# V1_USB_sch.net
KiCad netlist of a schematic drawn in Altium Designer
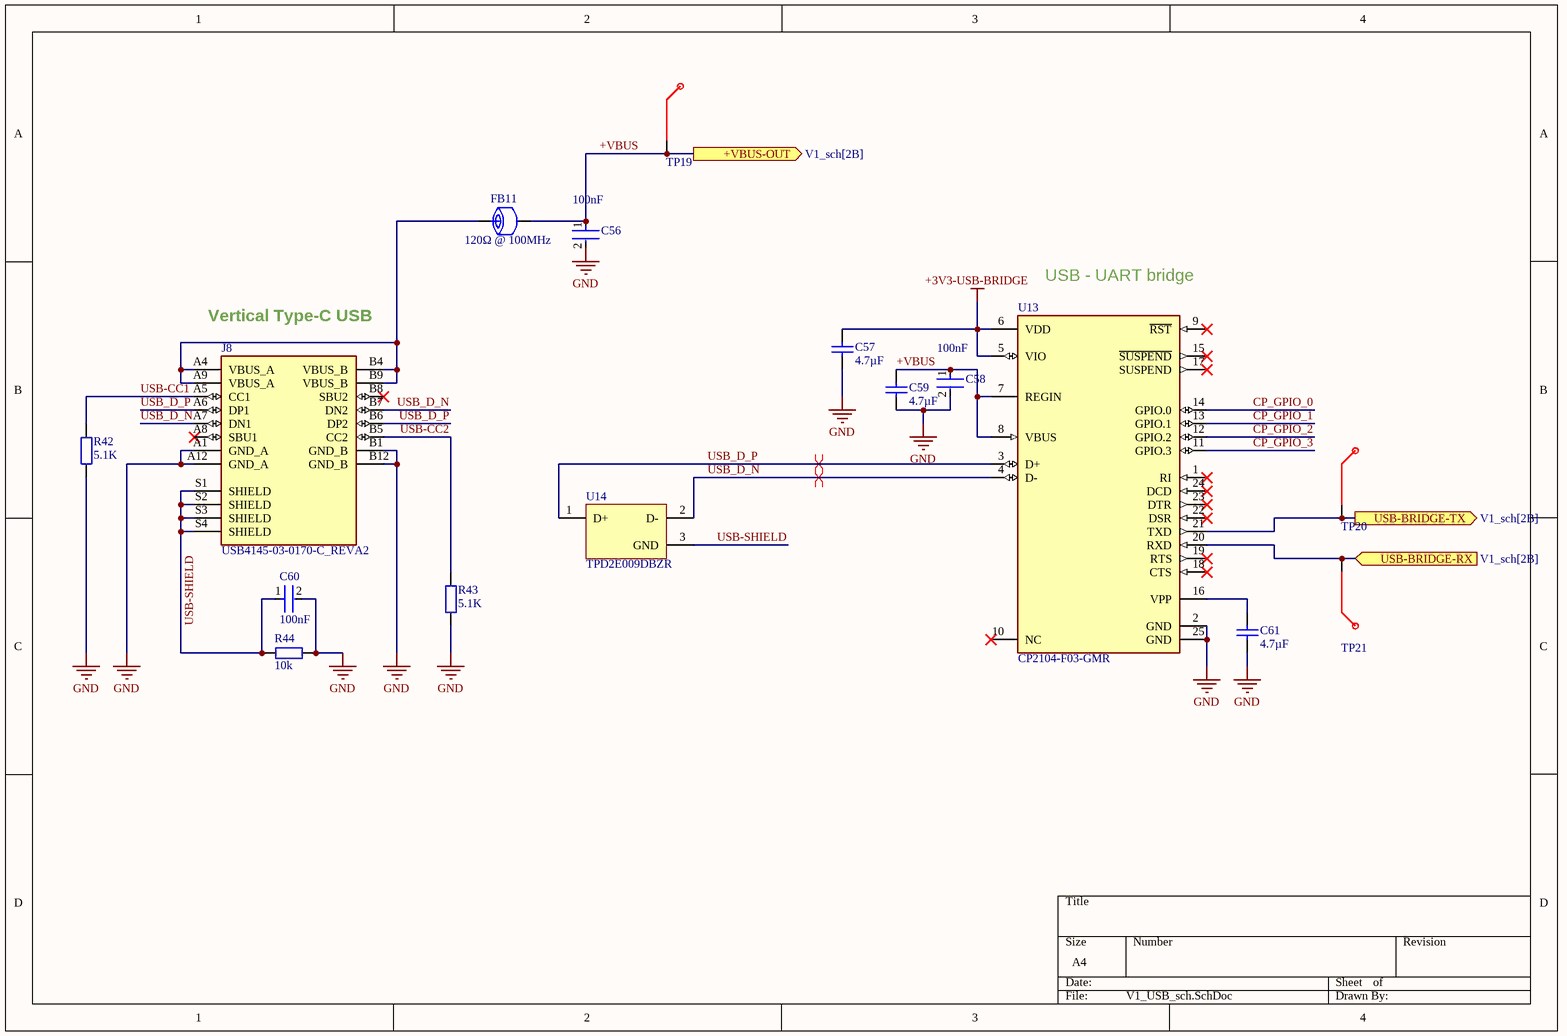
[diagram p0: V1_USB_sch.SchDoc]

(export (version "E")
  (design (tool "Eeschema 10.0.6"))
  (components
    (comp (ref "C56")
      (value "885012206095")
      (footprint "FP-885012206095-IPC_B")
      (description "CAP CER 0.1UF 50V X7R 0603")
      (fields (field (name "TOLERANCE") "10%") (field (name "CAPACITANCE") "100nF"))
      (libsource (lib "Altium Content Vault") (part "11868f565c42a9108669ba33697ecf6"))
    )
    (comp (ref "C57")
      (value "885012107018")
      (footprint "WCAP-CSGP_0805_L2W1.25H1.25")
      (description "WCAP-CSGP Multilayer Ceramic Chip Capacitor, General Purpose, size 0805, X5R, 4.7µF, 25VDC")
      (fields (field (name "MANUFACTURER") "Wurth Elektronik") (field (name "CAPACITANCE") "4.7µF"))
      (libsource (lib "Altium_WCAP-CSGP (rev22f)") (part "885012107018"))
    )
    (comp (ref "C58")
      (value "885012206095")
      (footprint "FP-885012206095-IPC_B")
      (description "CAP CER 0.1UF 50V X7R 0603")
      (fields (field (name "TOLERANCE") "10%") (field (name "CAPACITANCE") "100nF"))
      (libsource (lib "Altium Content Vault") (part "11868f565c42a9108669ba33697ecf6"))
    )
    (comp (ref "C59")
      (value "885012107018")
      (footprint "WCAP-CSGP_0805_L2W1.25H1.25")
      (description "WCAP-CSGP Multilayer Ceramic Chip Capacitor, General Purpose, size 0805, X5R, 4.7µF, 25VDC")
      (fields (field (name "MANUFACTURER") "Wurth Elektronik") (field (name "CAPACITANCE") "4.7µF"))
      (libsource (lib "Altium_WCAP-CSGP (rev22f)") (part "885012107018"))
    )
    (comp (ref "C60")
      (value "885012206095")
      (footprint "FP-885012206095-IPC_B")
      (description "CAP CER 0.1UF 50V X7R 0603")
      (fields (field (name "TOLERANCE") "10%") (field (name "CAPACITANCE") "100nF"))
      (libsource (lib "Altium Content Vault") (part "11868f565c42a9108669ba33697ecf6"))
    )
    (comp (ref "C61")
      (value "885012107018")
      (footprint "WCAP-CSGP_0805_L2W1.25H1.25")
      (description "WCAP-CSGP Multilayer Ceramic Chip Capacitor, General Purpose, size 0805, X5R, 4.7µF, 25VDC")
      (fields (field (name "MANUFACTURER") "Wurth Elektronik") (field (name "CAPACITANCE") "4.7µF"))
      (libsource (lib "Altium_WCAP-CSGP (rev22f)") (part "885012107018"))
    )
    (comp (ref "FB11")
      (value "120Ω @ 100MHz")
      (footprint "SMD_0805")
      (description "Ferrite Bead, 0805 [2012 Metric], 120 ohm, 800 mA, BLM21A Series, 0.15 ohm, ± 25%")
      (fields (field (name "MANUFACTURER") "Murata"))
      (libsource (lib "DAQ_REV_B") (part "BLM21AG121SN1D"))
    )
    (comp (ref "J8")
      (value "USB4145-03-0170-C_REVA2")
      (footprint "GCT_USB4145-03-0170-C_REVA2")
      (libsource (lib "USB4145-03-0170-C_REVA2") (part "USB4145-03-0170-C_REVA2"))
    )
    (comp (ref "R42")
      (value "5.1K")
      (footprint "Passives:FPR_0603_R_R0")
      (description "Resistor - generic SMD")
      (fields (field (name "Comment") "PN_R0603_5k1"))
      (libsource (lib "Passives") (part "R"))
    )
    (comp (ref "R43")
      (value "5.1K")
      (footprint "Passives:FPR_0603_R_R0")
      (description "Resistor - generic SMD")
      (fields (field (name "Comment") "PN_R0603_5k1"))
      (libsource (lib "Passives") (part "R"))
    )
    (comp (ref "R44")
      (value "10k")
      (footprint "Passives:FPR_0603_R_R0")
      (description "Resistor - generic SMD")
      (fields (field (name "Comment") "PN_R0603_10k"))
      (libsource (lib "Passives") (part "R"))
    )
    (comp (ref "TP19")
      (value "Test Point")
      (footprint "Test Point 1.5mm SMD")
      (libsource (lib "planinsekLib_sch") (part "Test Point"))
    )
    (comp (ref "TP20")
      (value "Test Point")
      (footprint "Test Point 1.5mm SMD")
      (libsource (lib "planinsekLib_sch") (part "Test Point"))
    )
    (comp (ref "TP21")
      (value "Test Point")
      (footprint "Test Point 1.5mm SMD")
      (libsource (lib "planinsekLib_sch") (part "Test Point"))
    )
    (comp (ref "U13")
      (value "CP2104-F03-GMR")
      (footprint "FP-CP2104-F03-GMR-IPC_A")
      (description "IC SGL USB-TO-UART BRIDGE 24QFN")
      (fields
        (field (name "OCTOPART") "https://octopart.com/cp2104-f03-gmr-silicon+labs-19668642")
        (field (name "MANUFACTURER") "Silicon Laboratories")
      )
      (libsource (lib "Altium Content Vault") (part "c264a613fa4ce846ece45e07ca4b292"))
    )
    (comp (ref "U14")
      (value "TPD2E009DBZR")
      (footprint "DBZ0003A_L")
      (fields (field (name "MANUFACTURER") "Texas Instruments"))
      (libsource (lib "Altium Content Vault") (part "TI-TPD2E009-SOT-23_DBZ-3"))
    )
  )
  (nets
    (net (code "1") (name "+3V3-USB-BRIDGE") (class "Default")
      (node (ref "C57") (pin "2") (pinfunction "2_2") (pintype "passive"))
      (node (ref "U13") (pin "5") (pinfunction "VIO_5") (pintype "bidirectional"))
      (node (ref "U13") (pin "6") (pinfunction "VDD_6") (pintype "power_in"))
    )
    (net (code "2") (name "/+VBUS") (class "Default")
      (node (ref "C56") (pin "1") (pinfunction "1_1") (pintype "passive"))
      (node (ref "C58") (pin "1") (pinfunction "1_1") (pintype "passive"))
      (node (ref "C59") (pin "2") (pinfunction "2_2") (pintype "passive"))
      (node (ref "FB11") (pin "2") (pintype "passive"))
      (node (ref "TP19") (pin "1") (pintype "passive"))
      (node (ref "U13") (pin "7") (pinfunction "REGIN_7") (pintype "power_in"))
      (node (ref "U13") (pin "8") (pinfunction "VBUS_8") (pintype "input"))
    )
    (net (code "3") (name "/CP_GPIO_0") (class "Default")
      (node (ref "U13") (pin "14") (pinfunction "GPIO.0_14") (pintype "bidirectional"))
    )
    (net (code "4") (name "/CP_GPIO_1") (class "Default")
      (node (ref "U13") (pin "13") (pinfunction "GPIO.1_13") (pintype "bidirectional"))
    )
    (net (code "5") (name "/CP_GPIO_2") (class "Default")
      (node (ref "U13") (pin "12") (pinfunction "GPIO.2_12") (pintype "bidirectional"))
    )
    (net (code "6") (name "/CP_GPIO_3") (class "Default")
      (node (ref "U13") (pin "11") (pinfunction "GPIO.3_11") (pintype "bidirectional"))
    )
    (net (code "7") (name "/USB-BRIDGE-RX") (class "Default")
      (node (ref "TP21") (pin "1") (pintype "passive"))
      (node (ref "U13") (pin "20") (pinfunction "RXD_20") (pintype "input"))
    )
    (net (code "8") (name "/USB-BRIDGE-TX") (class "Default")
      (node (ref "TP20") (pin "1") (pintype "passive"))
      (node (ref "U13") (pin "21") (pinfunction "TXD_21") (pintype "output"))
    )
    (net (code "9") (name "/USB-CC1") (class "Default")
      (node (ref "J8") (pin "A5") (pinfunction "CC1_A5") (pintype "bidirectional"))
      (node (ref "R42") (pin "1") (pinfunction "1_1") (pintype "passive"))
    )
    (net (code "10") (name "/USB-CC2") (class "Default")
      (node (ref "J8") (pin "B5") (pinfunction "CC2_B5") (pintype "bidirectional"))
      (node (ref "R43") (pin "1") (pinfunction "1_1") (pintype "passive"))
    )
    (net (code "11") (name "/USB-SHIELD") (class "Default")
      (node (ref "C60") (pin "1") (pinfunction "1_1") (pintype "passive"))
      (node (ref "J8") (pin "S1") (pinfunction "SHIELD_S1") (pintype "passive"))
      (node (ref "J8") (pin "S2") (pinfunction "SHIELD_S2") (pintype "passive"))
      (node (ref "J8") (pin "S3") (pinfunction "SHIELD_S3") (pintype "passive"))
      (node (ref "J8") (pin "S4") (pinfunction "SHIELD_S4") (pintype "passive"))
      (node (ref "R44") (pin "2") (pinfunction "2_2") (pintype "passive"))
      (node (ref "U14") (pin "3") (pinfunction "GND_3") (pintype "power_in"))
    )
    (net (code "12") (name "/USB_D_N") (class "Default")
      (node (ref "J8") (pin "A7") (pinfunction "DN1_A7") (pintype "bidirectional"))
      (node (ref "J8") (pin "B7") (pinfunction "DN2_B7") (pintype "bidirectional"))
      (node (ref "U13") (pin "4") (pinfunction "D-_4") (pintype "bidirectional"))
      (node (ref "U14") (pin "2") (pinfunction "D-_2") (pintype "passive"))
    )
    (net (code "13") (name "/USB_D_P") (class "Default")
      (node (ref "J8") (pin "A6") (pinfunction "DP1_A6") (pintype "bidirectional"))
      (node (ref "J8") (pin "B6") (pinfunction "DP2_B6") (pintype "bidirectional"))
      (node (ref "U13") (pin "3") (pinfunction "D+_3") (pintype "bidirectional"))
      (node (ref "U14") (pin "1") (pinfunction "D+_1") (pintype "passive"))
    )
    (net (code "14") (name "GND") (class "Default")
      (node (ref "C56") (pin "2") (pinfunction "2_2") (pintype "passive"))
      (node (ref "C57") (pin "1") (pinfunction "1_1") (pintype "passive"))
      (node (ref "C58") (pin "2") (pinfunction "2_2") (pintype "passive"))
      (node (ref "C59") (pin "1") (pinfunction "1_1") (pintype "passive"))
      (node (ref "C60") (pin "2") (pinfunction "2_2") (pintype "passive"))
      (node (ref "C61") (pin "1") (pinfunction "1_1") (pintype "passive"))
      (node (ref "J8") (pin "A1") (pinfunction "GND_A_A1") (pintype "power_in"))
      (node (ref "J8") (pin "A12") (pinfunction "GND_A_A12") (pintype "power_in"))
      (node (ref "J8") (pin "B1") (pinfunction "GND_B_B1") (pintype "power_in"))
      (node (ref "J8") (pin "B12") (pinfunction "GND_B_B12") (pintype "power_in"))
      (node (ref "R42") (pin "2") (pinfunction "2_2") (pintype "passive"))
      (node (ref "R43") (pin "2") (pinfunction "2_2") (pintype "passive"))
      (node (ref "R44") (pin "1") (pinfunction "1_1") (pintype "passive"))
      (node (ref "U13") (pin "2") (pinfunction "GND_2") (pintype "power_in"))
      (node (ref "U13") (pin "25") (pinfunction "GND_25") (pintype "power_in"))
    )
    (net (code "15") (name "Net-(FB11-Pad1)") (class "Default")
      (node (ref "FB11") (pin "1") (pintype "passive"))
      (node (ref "J8") (pin "A4") (pinfunction "VBUS_A_A4") (pintype "power_in"))
      (node (ref "J8") (pin "A9") (pinfunction "VBUS_A_A9") (pintype "power_in"))
      (node (ref "J8") (pin "B4") (pinfunction "VBUS_B_B4") (pintype "power_in"))
      (node (ref "J8") (pin "B9") (pinfunction "VBUS_B_B9") (pintype "power_in"))
    )
    (net (code "16") (name "Net-(U13-VPP)") (class "Default")
      (node (ref "C61") (pin "2") (pinfunction "2_2") (pintype "passive"))
      (node (ref "U13") (pin "16") (pinfunction "VPP_16") (pintype "power_in"))
    )
    (net (code "17") (name "unconnected-(J8-SBU1-PadA8)") (class "Default")
      (node (ref "J8") (pin "A8") (pinfunction "SBU1_A8") (pintype "bidirectional+no_connect"))
    )
    (net (code "18") (name "unconnected-(J8-SBU2-PadB8)") (class "Default")
      (node (ref "J8") (pin "B8") (pinfunction "SBU2_B8") (pintype "bidirectional+no_connect"))
    )
    (net (code "19") (name "unconnected-(U13-CTS-Pad18)") (class "Default")
      (node (ref "U13") (pin "18") (pinfunction "CTS_18") (pintype "input+no_connect"))
    )
    (net (code "20") (name "unconnected-(U13-DCD-Pad24)") (class "Default")
      (node (ref "U13") (pin "24") (pinfunction "DCD_24") (pintype "input+no_connect"))
    )
    (net (code "21") (name "unconnected-(U13-DSR-Pad22)") (class "Default")
      (node (ref "U13") (pin "22") (pinfunction "DSR_22") (pintype "input+no_connect"))
    )
    (net (code "22") (name "unconnected-(U13-DTR-Pad23)") (class "Default")
      (node (ref "U13") (pin "23") (pinfunction "DTR_23") (pintype "output+no_connect"))
    )
    (net (code "23") (name "unconnected-(U13-NC-Pad10)") (class "Default")
      (node (ref "U13") (pin "10") (pinfunction "NC_10") (pintype "passive+no_connect"))
    )
    (net (code "24") (name "unconnected-(U13-RI-Pad1)") (class "Default")
      (node (ref "U13") (pin "1") (pinfunction "RI_1") (pintype "input+no_connect"))
    )
    (net (code "25") (name "unconnected-(U13-RTS-Pad19)") (class "Default")
      (node (ref "U13") (pin "19") (pinfunction "RTS_19") (pintype "output+no_connect"))
    )
    (net (code "26") (name "unconnected-(U13-SUSPEND-Pad17)") (class "Default")
      (node (ref "U13") (pin "17") (pinfunction "SUSPEND_17") (pintype "output+no_connect"))
    )
    (net (code "27") (name "unconnected-(U13-~{RST}-Pad9)") (class "Default")
      (node (ref "U13") (pin "9") (pinfunction "~{RST}_9") (pintype "input+no_connect"))
    )
    (net (code "28") (name "unconnected-(U13-~{SUSPEND}-Pad15)") (class "Default")
      (node (ref "U13") (pin "15") (pinfunction "~{SUSPEND}_15") (pintype "output+no_connect"))
    )
  )
)
